# 2.net
KiCad netlist of a schematic drawn in EasyEDA
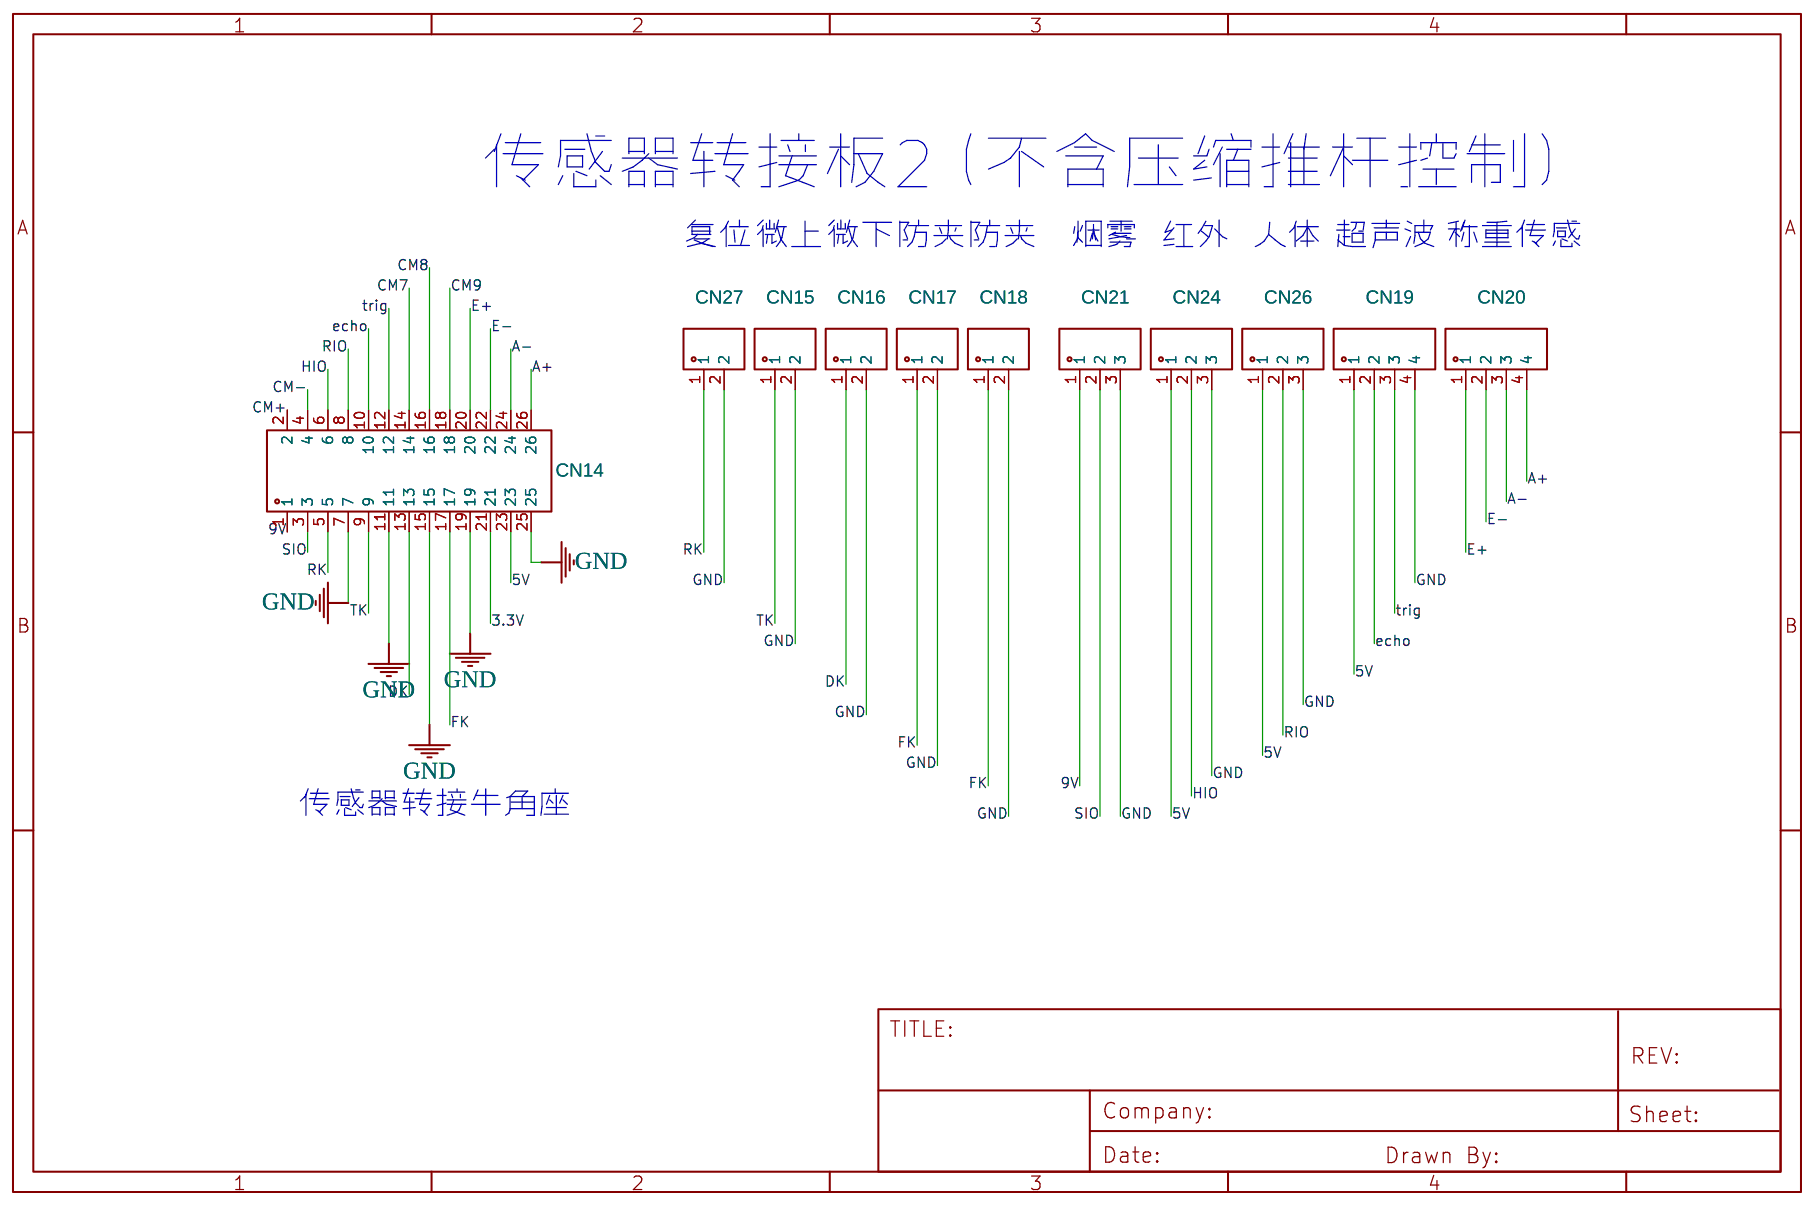
[diagram p0: schematic sheet]

(export (version "E")
  (design (tool "Eeschema 10.0.6"))
  (components
    (comp (ref "CN14")
      (value "Shenzhen")
      (fields
        (field (name "BOM_Manufacturer Part") "B-3000S26P-0110")
        (field (name "BOM_Supplier Part") "C383600")
      )
      (libsource (lib "") (part "B-3000S26P-0110"))
    )
    (comp (ref "CN15")
      (value "KF2EDGR-2.54-2P")
      (fields (field (name "BOM_Supplier Part") "C577594"))
      (libsource (lib "") (part "KF2EDGR-2.54-2P"))
    )
    (comp (ref "CN16")
      (value "KF2EDGR-2.54-2P")
      (fields (field (name "BOM_Supplier Part") "C577594"))
      (libsource (lib "") (part "KF2EDGR-2.54-2P"))
    )
    (comp (ref "CN17")
      (value "KF2EDGR-2.54-2P")
      (fields (field (name "BOM_Supplier Part") "C577594"))
      (libsource (lib "") (part "KF2EDGR-2.54-2P"))
    )
    (comp (ref "CN18")
      (value "KF2EDGR-2.54-2P")
      (fields (field (name "BOM_Supplier Part") "C577594"))
      (libsource (lib "") (part "KF2EDGR-2.54-2P"))
    )
    (comp (ref "CN19")
      (value "KF2EDGR-2.54-4P")
      (fields (field (name "BOM_Supplier Part") "C577596"))
      (libsource (lib "") (part "KF2EDGR-2.54-4P"))
    )
    (comp (ref "CN20")
      (value "KF2EDGR-2.54-4P")
      (fields (field (name "BOM_Supplier Part") "C577596"))
      (libsource (lib "") (part "KF2EDGR-2.54-4P"))
    )
    (comp (ref "CN21")
      (value "KF2EDGR-2.54-3P")
      (fields (field (name "BOM_Supplier Part") "C577595"))
      (libsource (lib "") (part "KF2EDGR-2.54-3P"))
    )
    (comp (ref "CN24")
      (value "KF2EDGR-2.54-3P")
      (fields (field (name "BOM_Supplier Part") "C577595"))
      (libsource (lib "") (part "KF2EDGR-2.54-3P"))
    )
    (comp (ref "CN26")
      (value "KF2EDGR-2.54-3P")
      (fields (field (name "BOM_Supplier Part") "C577595"))
      (libsource (lib "") (part "KF2EDGR-2.54-3P"))
    )
    (comp (ref "CN27")
      (value "KF2EDGR-2.54-2P")
      (fields (field (name "BOM_Supplier Part") "C577594"))
      (libsource (lib "") (part "KF2EDGR-2.54-2P"))
    )
  )
  (nets
    (net (code "1") (name "/3.3V") (class "Default")
      (node (ref "CN14") (pin "21") (pinfunction "21_21") (pintype "unspecified"))
    )
    (net (code "2") (name "/5V") (class "Default")
      (node (ref "CN14") (pin "23") (pinfunction "23_23") (pintype "unspecified"))
      (node (ref "CN19") (pin "1") (pinfunction "1_1") (pintype "unspecified"))
      (node (ref "CN24") (pin "1") (pinfunction "1_1") (pintype "unspecified"))
      (node (ref "CN26") (pin "1") (pinfunction "1_1") (pintype "unspecified"))
    )
    (net (code "3") (name "/9V") (class "Default")
      (node (ref "CN14") (pin "1") (pinfunction "1_1") (pintype "unspecified"))
      (node (ref "CN21") (pin "1") (pinfunction "1_1") (pintype "unspecified"))
    )
    (net (code "4") (name "/A+") (class "Default")
      (node (ref "CN14") (pin "26") (pinfunction "26_26") (pintype "unspecified"))
      (node (ref "CN20") (pin "4") (pinfunction "4_4") (pintype "unspecified"))
    )
    (net (code "5") (name "/A-") (class "Default")
      (node (ref "CN14") (pin "24") (pinfunction "24_24") (pintype "unspecified"))
      (node (ref "CN20") (pin "3") (pinfunction "3_3") (pintype "unspecified"))
    )
    (net (code "6") (name "/CM+") (class "Default")
      (node (ref "CN14") (pin "2") (pinfunction "2_2") (pintype "unspecified"))
    )
    (net (code "7") (name "/CM-") (class "Default")
      (node (ref "CN14") (pin "4") (pinfunction "4_4") (pintype "unspecified"))
    )
    (net (code "8") (name "/CM7") (class "Default")
      (node (ref "CN14") (pin "14") (pinfunction "14_14") (pintype "unspecified"))
    )
    (net (code "9") (name "/CM8") (class "Default")
      (node (ref "CN14") (pin "16") (pinfunction "16_16") (pintype "unspecified"))
    )
    (net (code "10") (name "/CM9") (class "Default")
      (node (ref "CN14") (pin "18") (pinfunction "18_18") (pintype "unspecified"))
    )
    (net (code "11") (name "/DK") (class "Default")
      (node (ref "CN14") (pin "13") (pinfunction "13_13") (pintype "unspecified"))
      (node (ref "CN16") (pin "1") (pinfunction "1_1") (pintype "unspecified"))
    )
    (net (code "12") (name "/E+") (class "Default")
      (node (ref "CN14") (pin "20") (pinfunction "20_20") (pintype "unspecified"))
      (node (ref "CN20") (pin "1") (pinfunction "1_1") (pintype "unspecified"))
    )
    (net (code "13") (name "/E-") (class "Default")
      (node (ref "CN14") (pin "22") (pinfunction "22_22") (pintype "unspecified"))
      (node (ref "CN20") (pin "2") (pinfunction "2_2") (pintype "unspecified"))
    )
    (net (code "14") (name "/FK") (class "Default")
      (node (ref "CN14") (pin "17") (pinfunction "17_17") (pintype "unspecified"))
      (node (ref "CN17") (pin "1") (pinfunction "1_1") (pintype "unspecified"))
      (node (ref "CN18") (pin "1") (pinfunction "1_1") (pintype "unspecified"))
    )
    (net (code "15") (name "/HIO") (class "Default")
      (node (ref "CN14") (pin "6") (pinfunction "6_6") (pintype "unspecified"))
      (node (ref "CN24") (pin "2") (pinfunction "2_2") (pintype "unspecified"))
    )
    (net (code "16") (name "/RIO") (class "Default")
      (node (ref "CN14") (pin "8") (pinfunction "8_8") (pintype "unspecified"))
      (node (ref "CN26") (pin "2") (pinfunction "2_2") (pintype "unspecified"))
    )
    (net (code "17") (name "/RK") (class "Default")
      (node (ref "CN14") (pin "5") (pinfunction "5_5") (pintype "unspecified"))
      (node (ref "CN27") (pin "1") (pinfunction "1_1") (pintype "unspecified"))
    )
    (net (code "18") (name "/SIO") (class "Default")
      (node (ref "CN14") (pin "3") (pinfunction "3_3") (pintype "unspecified"))
      (node (ref "CN21") (pin "2") (pinfunction "2_2") (pintype "unspecified"))
    )
    (net (code "19") (name "/TK") (class "Default")
      (node (ref "CN14") (pin "9") (pinfunction "9_9") (pintype "unspecified"))
      (node (ref "CN15") (pin "1") (pinfunction "1_1") (pintype "unspecified"))
    )
    (net (code "20") (name "/echo") (class "Default")
      (node (ref "CN14") (pin "10") (pinfunction "10_10") (pintype "unspecified"))
      (node (ref "CN19") (pin "2") (pinfunction "2_2") (pintype "unspecified"))
    )
    (net (code "21") (name "/trig") (class "Default")
      (node (ref "CN14") (pin "12") (pinfunction "12_12") (pintype "unspecified"))
      (node (ref "CN19") (pin "3") (pinfunction "3_3") (pintype "unspecified"))
    )
    (net (code "22") (name "GND") (class "Default")
      (node (ref "CN14") (pin "11") (pinfunction "11_11") (pintype "unspecified"))
      (node (ref "CN14") (pin "15") (pinfunction "15_15") (pintype "unspecified"))
      (node (ref "CN14") (pin "19") (pinfunction "19_19") (pintype "unspecified"))
      (node (ref "CN14") (pin "25") (pinfunction "25_25") (pintype "unspecified"))
      (node (ref "CN14") (pin "7") (pinfunction "7_7") (pintype "unspecified"))
      (node (ref "CN15") (pin "2") (pinfunction "2_2") (pintype "unspecified"))
      (node (ref "CN16") (pin "2") (pinfunction "2_2") (pintype "unspecified"))
      (node (ref "CN17") (pin "2") (pinfunction "2_2") (pintype "unspecified"))
      (node (ref "CN18") (pin "2") (pinfunction "2_2") (pintype "unspecified"))
      (node (ref "CN19") (pin "4") (pinfunction "4_4") (pintype "unspecified"))
      (node (ref "CN21") (pin "3") (pinfunction "3_3") (pintype "unspecified"))
      (node (ref "CN24") (pin "3") (pinfunction "3_3") (pintype "unspecified"))
      (node (ref "CN26") (pin "3") (pinfunction "3_3") (pintype "unspecified"))
      (node (ref "CN27") (pin "2") (pinfunction "2_2") (pintype "unspecified"))
    )
  )
)
